# Borealis_DMX_Pixel.net
KiCad netlist of a schematic drawn in EAGLE
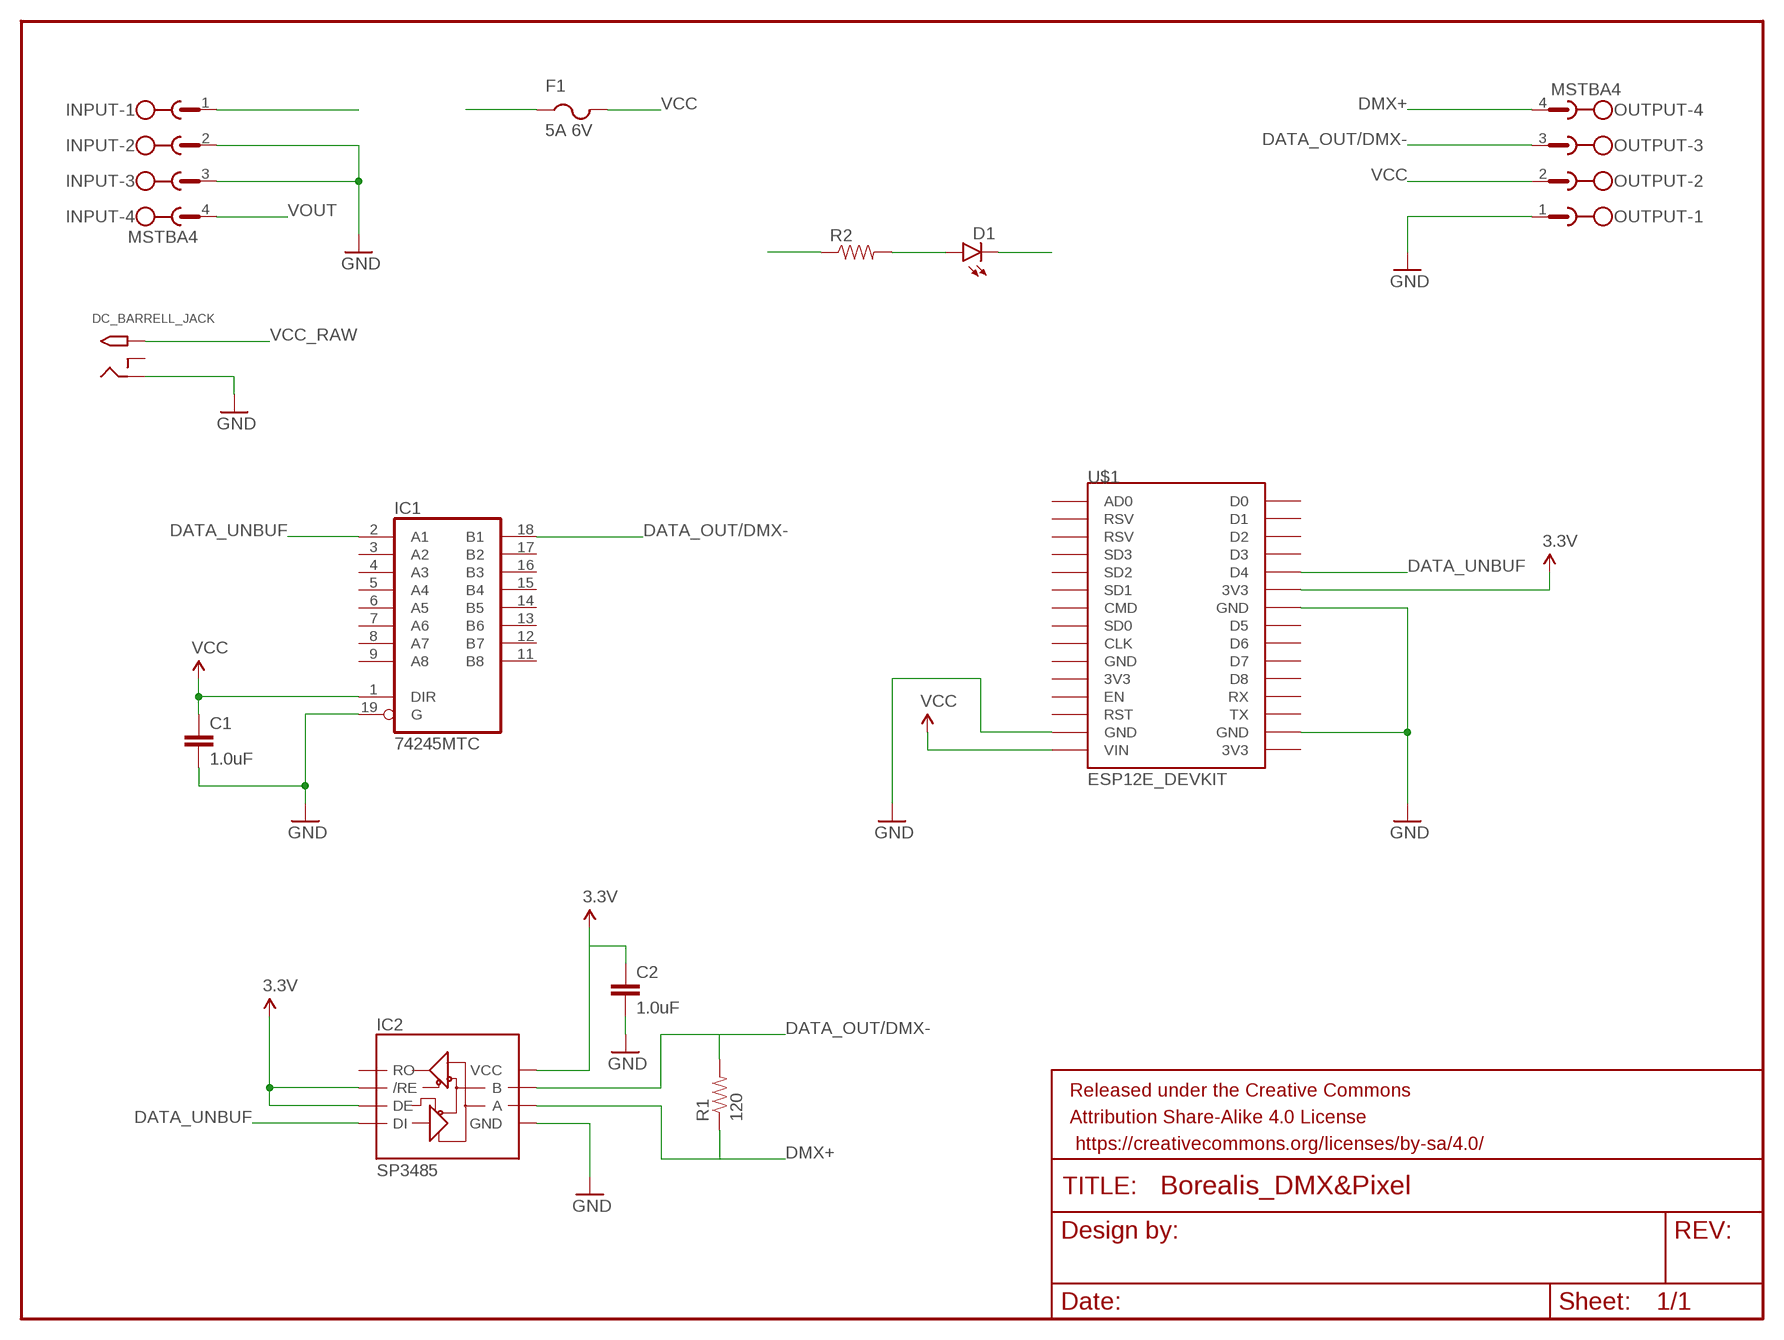
[diagram p0: schematic, sheet 1]

(export (version "E")
  (design (tool "Eeschema 10.0.6"))
  (components
    (comp (ref "C1")
      (value "1.0uF")
      (footprint "eagle-import:0603-CAP")
      (libsource (lib "eagle-import") (part "1.0UF-16V-10%(0603)"))
    )
    (comp (ref "C2")
      (value "1.0uF")
      (footprint "eagle-import:0603-CAP")
      (libsource (lib "eagle-import") (part "1.0UF-16V-10%(0603)"))
    )
    (comp (ref "D1")
      (value "LED1206-BOTTOM")
      (footprint "eagle-import:LED-1206-BOTTOM")
      (libsource (lib "eagle-import") (part "LED1206-BOTTOM"))
    )
    (comp (ref "DC_BARRELL_JACK")
      (value "2.1MMJACKTHM")
      (footprint "eagle-import:PJ-102A")
      (libsource (lib "eagle-import") (part "2.1MMJACKTHM"))
    )
    (comp (ref "F1")
      (value "5A 6V")
      (footprint "eagle-import:R1206")
      (libsource (lib "eagle-import") (part "PTCFUSE-1206"))
    )
    (comp (ref "FRAME1")
      (value "FRAME-LETTERNO_PACKAGE")
      (footprint "eagle-import:DUMMY")
      (fields (field (name "DESIGNER") "Nobody"))
      (libsource (lib "eagle-import") (part "FRAME-LETTERNO_PACKAGE"))
    )
    (comp (ref "IC1")
      (value "74245MTC")
      (footprint "eagle-import:SSOP20")
      (libsource (lib "eagle-import") (part "74245MTC"))
    )
    (comp (ref "IC2")
      (value "SP3485")
      (footprint "eagle-import:SO08")
      (libsource (lib "eagle-import") (part "RS485SOIC"))
    )
    (comp (ref "INPUT")
      (value "MSTBA4")
      (footprint "eagle-import:MSTBA4")
      (fields (field (name "MF") "FARNELL") (field (name "MPN") "1757268"))
      (libsource (lib "eagle-import") (part "MSTBA4"))
    )
    (comp (ref "OUTPUT")
      (value "MSTBA4")
      (footprint "eagle-import:MSTBA4")
      (fields (field (name "MF") "FARNELL") (field (name "MPN") "1757268"))
      (libsource (lib "eagle-import") (part "MSTBA4"))
    )
    (comp (ref "R1")
      (value "120")
      (footprint "eagle-import:0603-RES")
      (libsource (lib "eagle-import") (part "RESISTOR0603"))
    )
    (comp (ref "R2")
      (value "RESISTOR0603-RES")
      (footprint "eagle-import:0603-RES")
      (libsource (lib "eagle-import") (part "RESISTOR0603-RES"))
    )
    (comp (ref "U$1")
      (value "ESP12E_DEVKIT")
      (footprint "eagle-import:DEV_LAYOUT")
      (libsource (lib "eagle-import") (part "ESP12E_DEVKIT"))
    )
  )
  (nets
    (net (code "1") (name "/DATA_OUT{slash}DMX-") (class "Default")
      (node (ref "IC1") (pin "18") (pinfunction "B1_18") (pintype "bidirectional"))
      (node (ref "IC2") (pin "7") (pinfunction "B_7") (pintype "bidirectional"))
      (node (ref "OUTPUT") (pin "3") (pinfunction "1_3") (pintype "passive"))
      (node (ref "R1") (pin "2") (pinfunction "2_2") (pintype "passive"))
    )
    (net (code "2") (name "/DATA_UNBUF") (class "Default")
      (node (ref "IC1") (pin "2") (pinfunction "A1_2") (pintype "bidirectional"))
      (node (ref "IC2") (pin "4") (pinfunction "DI_4") (pintype "bidirectional"))
      (node (ref "U$1") (pin "D4") (pinfunction "D4_D4") (pintype "bidirectional"))
    )
    (net (code "3") (name "/DMX+") (class "Default")
      (node (ref "IC2") (pin "6") (pinfunction "A_6") (pintype "bidirectional"))
      (node (ref "OUTPUT") (pin "4") (pinfunction "1_4") (pintype "passive"))
      (node (ref "R1") (pin "1") (pinfunction "1_1") (pintype "passive"))
    )
    (net (code "4") (name "/VCC_RAW") (class "Default")
      (node (ref "DC_BARRELL_JACK") (pin "TIP") (pinfunction "TIP_TIP") (pintype "bidirectional"))
      (node (ref "F1") (pin "1") (pinfunction "1_1") (pintype "passive"))
      (node (ref "INPUT") (pin "1") (pinfunction "1_1") (pintype "passive"))
    )
    (net (code "5") (name "/VOUT") (class "Default")
      (node (ref "INPUT") (pin "4") (pinfunction "1_4") (pintype "passive"))
    )
    (net (code "6") (name "3.3V") (class "Default")
      (node (ref "C2") (pin "1") (pinfunction "1_1") (pintype "passive"))
      (node (ref "IC2") (pin "2") (pinfunction "/RE_2") (pintype "bidirectional"))
      (node (ref "IC2") (pin "3") (pinfunction "DE_3") (pintype "bidirectional"))
      (node (ref "IC2") (pin "8") (pinfunction "VCC_8") (pintype "bidirectional"))
      (node (ref "U$1") (pin "3V3@1") (pinfunction "3V3_3V3@1") (pintype "bidirectional"))
    )
    (net (code "7") (name "GND") (class "Default")
      (node (ref "C1") (pin "2") (pinfunction "2_2") (pintype "passive"))
      (node (ref "C2") (pin "2") (pinfunction "2_2") (pintype "passive"))
      (node (ref "D1") (pin "C") (pinfunction "C_C") (pintype "passive"))
      (node (ref "DC_BARRELL_JACK") (pin "RING") (pinfunction "RING_RING") (pintype "bidirectional"))
      (node (ref "IC1") (pin "19") (pinfunction "G_19") (pintype "input"))
      (node (ref "IC2") (pin "5") (pinfunction "GND_5") (pintype "bidirectional"))
      (node (ref "INPUT") (pin "2") (pinfunction "1_2") (pintype "passive"))
      (node (ref "INPUT") (pin "3") (pinfunction "1_3") (pintype "passive"))
      (node (ref "OUTPUT") (pin "1") (pinfunction "1_1") (pintype "passive"))
      (node (ref "U$1") (pin "GND@1") (pinfunction "GND_GND@1") (pintype "bidirectional"))
      (node (ref "U$1") (pin "GND@2") (pinfunction "GND_GND@2") (pintype "bidirectional"))
      (node (ref "U$1") (pin "GND@3") (pinfunction "GND_GND@3") (pintype "bidirectional"))
    )
    (net (code "8") (name "Net-(D1-PadA)") (class "Default")
      (node (ref "D1") (pin "A") (pinfunction "A_A") (pintype "passive"))
      (node (ref "R2") (pin "2") (pinfunction "2_2") (pintype "passive"))
    )
    (net (code "9") (name "VCC") (class "Default")
      (node (ref "C1") (pin "1") (pinfunction "1_1") (pintype "passive"))
      (node (ref "F1") (pin "2") (pinfunction "2_2") (pintype "passive"))
      (node (ref "IC1") (pin "1") (pinfunction "DIR_1") (pintype "input"))
      (node (ref "OUTPUT") (pin "2") (pinfunction "1_2") (pintype "passive"))
      (node (ref "R2") (pin "1") (pinfunction "1_1") (pintype "passive"))
      (node (ref "U$1") (pin "VIN") (pinfunction "VIN_VIN") (pintype "bidirectional"))
    )
    (net (code "10") (name "unconnected-(DC_BARRELL_JACK-PadRING_SW)") (class "Default")
      (node (ref "DC_BARRELL_JACK") (pin "RING_SW") (pinfunction "RING_SW_RING_SW") (pintype "bidirectional"))
    )
    (net (code "11") (name "unconnected-(IC1A-A2-Pad3)") (class "Default")
      (node (ref "IC1") (pin "3") (pinfunction "A2_3") (pintype "bidirectional"))
    )
    (net (code "12") (name "unconnected-(IC1A-A3-Pad4)") (class "Default")
      (node (ref "IC1") (pin "4") (pinfunction "A3_4") (pintype "bidirectional"))
    )
    (net (code "13") (name "unconnected-(IC1A-A4-Pad5)") (class "Default")
      (node (ref "IC1") (pin "5") (pinfunction "A4_5") (pintype "bidirectional"))
    )
    (net (code "14") (name "unconnected-(IC1A-A5-Pad6)") (class "Default")
      (node (ref "IC1") (pin "6") (pinfunction "A5_6") (pintype "bidirectional"))
    )
    (net (code "15") (name "unconnected-(IC1A-A6-Pad7)") (class "Default")
      (node (ref "IC1") (pin "7") (pinfunction "A6_7") (pintype "bidirectional"))
    )
    (net (code "16") (name "unconnected-(IC1A-A7-Pad8)") (class "Default")
      (node (ref "IC1") (pin "8") (pinfunction "A7_8") (pintype "bidirectional"))
    )
    (net (code "17") (name "unconnected-(IC1A-A8-Pad9)") (class "Default")
      (node (ref "IC1") (pin "9") (pinfunction "A8_9") (pintype "bidirectional"))
    )
    (net (code "18") (name "unconnected-(IC1A-B2-Pad17)") (class "Default")
      (node (ref "IC1") (pin "17") (pinfunction "B2_17") (pintype "bidirectional"))
    )
    (net (code "19") (name "unconnected-(IC1A-B3-Pad16)") (class "Default")
      (node (ref "IC1") (pin "16") (pinfunction "B3_16") (pintype "bidirectional"))
    )
    (net (code "20") (name "unconnected-(IC1A-B4-Pad15)") (class "Default")
      (node (ref "IC1") (pin "15") (pinfunction "B4_15") (pintype "bidirectional"))
    )
    (net (code "21") (name "unconnected-(IC1A-B5-Pad14)") (class "Default")
      (node (ref "IC1") (pin "14") (pinfunction "B5_14") (pintype "bidirectional"))
    )
    (net (code "22") (name "unconnected-(IC1A-B6-Pad13)") (class "Default")
      (node (ref "IC1") (pin "13") (pinfunction "B6_13") (pintype "bidirectional"))
    )
    (net (code "23") (name "unconnected-(IC1A-B7-Pad12)") (class "Default")
      (node (ref "IC1") (pin "12") (pinfunction "B7_12") (pintype "bidirectional"))
    )
    (net (code "24") (name "unconnected-(IC1A-B8-Pad11)") (class "Default")
      (node (ref "IC1") (pin "11") (pinfunction "B8_11") (pintype "bidirectional"))
    )
    (net (code "25") (name "unconnected-(IC2-RO-Pad1)") (class "Default")
      (node (ref "IC2") (pin "1") (pinfunction "RO_1") (pintype "bidirectional"))
    )
    (net (code "26") (name "unconnected-(U$1-3V3-Pad3V3@0)") (class "Default")
      (node (ref "U$1") (pin "3V3@0") (pinfunction "3V3_3V3@0") (pintype "bidirectional"))
    )
    (net (code "27") (name "unconnected-(U$1-3V3-Pad3V3@2)") (class "Default")
      (node (ref "U$1") (pin "3V3@2") (pinfunction "3V3_3V3@2") (pintype "bidirectional"))
    )
    (net (code "28") (name "unconnected-(U$1-GND-PadGND@0)") (class "Default")
      (node (ref "U$1") (pin "GND@0") (pinfunction "GND_GND@0") (pintype "bidirectional"))
    )
    (net (code "29") (name "unconnected-(U$1-PadAD0)") (class "Default")
      (node (ref "U$1") (pin "AD0") (pinfunction "AD0_AD0") (pintype "bidirectional"))
    )
    (net (code "30") (name "unconnected-(U$1-PadCLK)") (class "Default")
      (node (ref "U$1") (pin "CLK") (pinfunction "CLK_CLK") (pintype "bidirectional"))
    )
    (net (code "31") (name "unconnected-(U$1-PadCMD)") (class "Default")
      (node (ref "U$1") (pin "CMD") (pinfunction "CMD_CMD") (pintype "bidirectional"))
    )
    (net (code "32") (name "unconnected-(U$1-PadD0)") (class "Default")
      (node (ref "U$1") (pin "D0") (pinfunction "D0_D0") (pintype "bidirectional"))
    )
    (net (code "33") (name "unconnected-(U$1-PadD1)") (class "Default")
      (node (ref "U$1") (pin "D1") (pinfunction "D1_D1") (pintype "bidirectional"))
    )
    (net (code "34") (name "unconnected-(U$1-PadD2)") (class "Default")
      (node (ref "U$1") (pin "D2") (pinfunction "D2_D2") (pintype "bidirectional"))
    )
    (net (code "35") (name "unconnected-(U$1-PadD3)") (class "Default")
      (node (ref "U$1") (pin "D3") (pinfunction "D3_D3") (pintype "bidirectional"))
    )
    (net (code "36") (name "unconnected-(U$1-PadD5)") (class "Default")
      (node (ref "U$1") (pin "D5") (pinfunction "D5_D5") (pintype "bidirectional"))
    )
    (net (code "37") (name "unconnected-(U$1-PadD6)") (class "Default")
      (node (ref "U$1") (pin "D6") (pinfunction "D6_D6") (pintype "bidirectional"))
    )
    (net (code "38") (name "unconnected-(U$1-PadD7)") (class "Default")
      (node (ref "U$1") (pin "D7") (pinfunction "D7_D7") (pintype "bidirectional"))
    )
    (net (code "39") (name "unconnected-(U$1-PadD8)") (class "Default")
      (node (ref "U$1") (pin "D8") (pinfunction "D8_D8") (pintype "bidirectional"))
    )
    (net (code "40") (name "unconnected-(U$1-PadEN)") (class "Default")
      (node (ref "U$1") (pin "EN") (pinfunction "EN_EN") (pintype "bidirectional"))
    )
    (net (code "41") (name "unconnected-(U$1-PadRST)") (class "Default")
      (node (ref "U$1") (pin "RST") (pinfunction "RST_RST") (pintype "bidirectional"))
    )
    (net (code "42") (name "unconnected-(U$1-PadRX)") (class "Default")
      (node (ref "U$1") (pin "RX") (pinfunction "RX_RX") (pintype "bidirectional"))
    )
    (net (code "43") (name "unconnected-(U$1-PadSD0)") (class "Default")
      (node (ref "U$1") (pin "SD0") (pinfunction "SD0_SD0") (pintype "bidirectional"))
    )
    (net (code "44") (name "unconnected-(U$1-PadSD1)") (class "Default")
      (node (ref "U$1") (pin "SD1") (pinfunction "SD1_SD1") (pintype "bidirectional"))
    )
    (net (code "45") (name "unconnected-(U$1-PadSD2)") (class "Default")
      (node (ref "U$1") (pin "SD2") (pinfunction "SD2_SD2") (pintype "bidirectional"))
    )
    (net (code "46") (name "unconnected-(U$1-PadSD3)") (class "Default")
      (node (ref "U$1") (pin "SD3") (pinfunction "SD3_SD3") (pintype "bidirectional"))
    )
    (net (code "47") (name "unconnected-(U$1-PadTX)") (class "Default")
      (node (ref "U$1") (pin "TX") (pinfunction "TX_TX") (pintype "bidirectional"))
    )
    (net (code "48") (name "unconnected-(U$1-RSV-PadRSV@0)") (class "Default")
      (node (ref "U$1") (pin "RSV@0") (pinfunction "RSV_RSV@0") (pintype "bidirectional"))
    )
    (net (code "49") (name "unconnected-(U$1-RSV-PadRSV@1)") (class "Default")
      (node (ref "U$1") (pin "RSV@1") (pinfunction "RSV_RSV@1") (pintype "bidirectional"))
    )
  )
)
